# Medidor_Sensor.net
KiCad netlist of a schematic drawn in Altium Designer
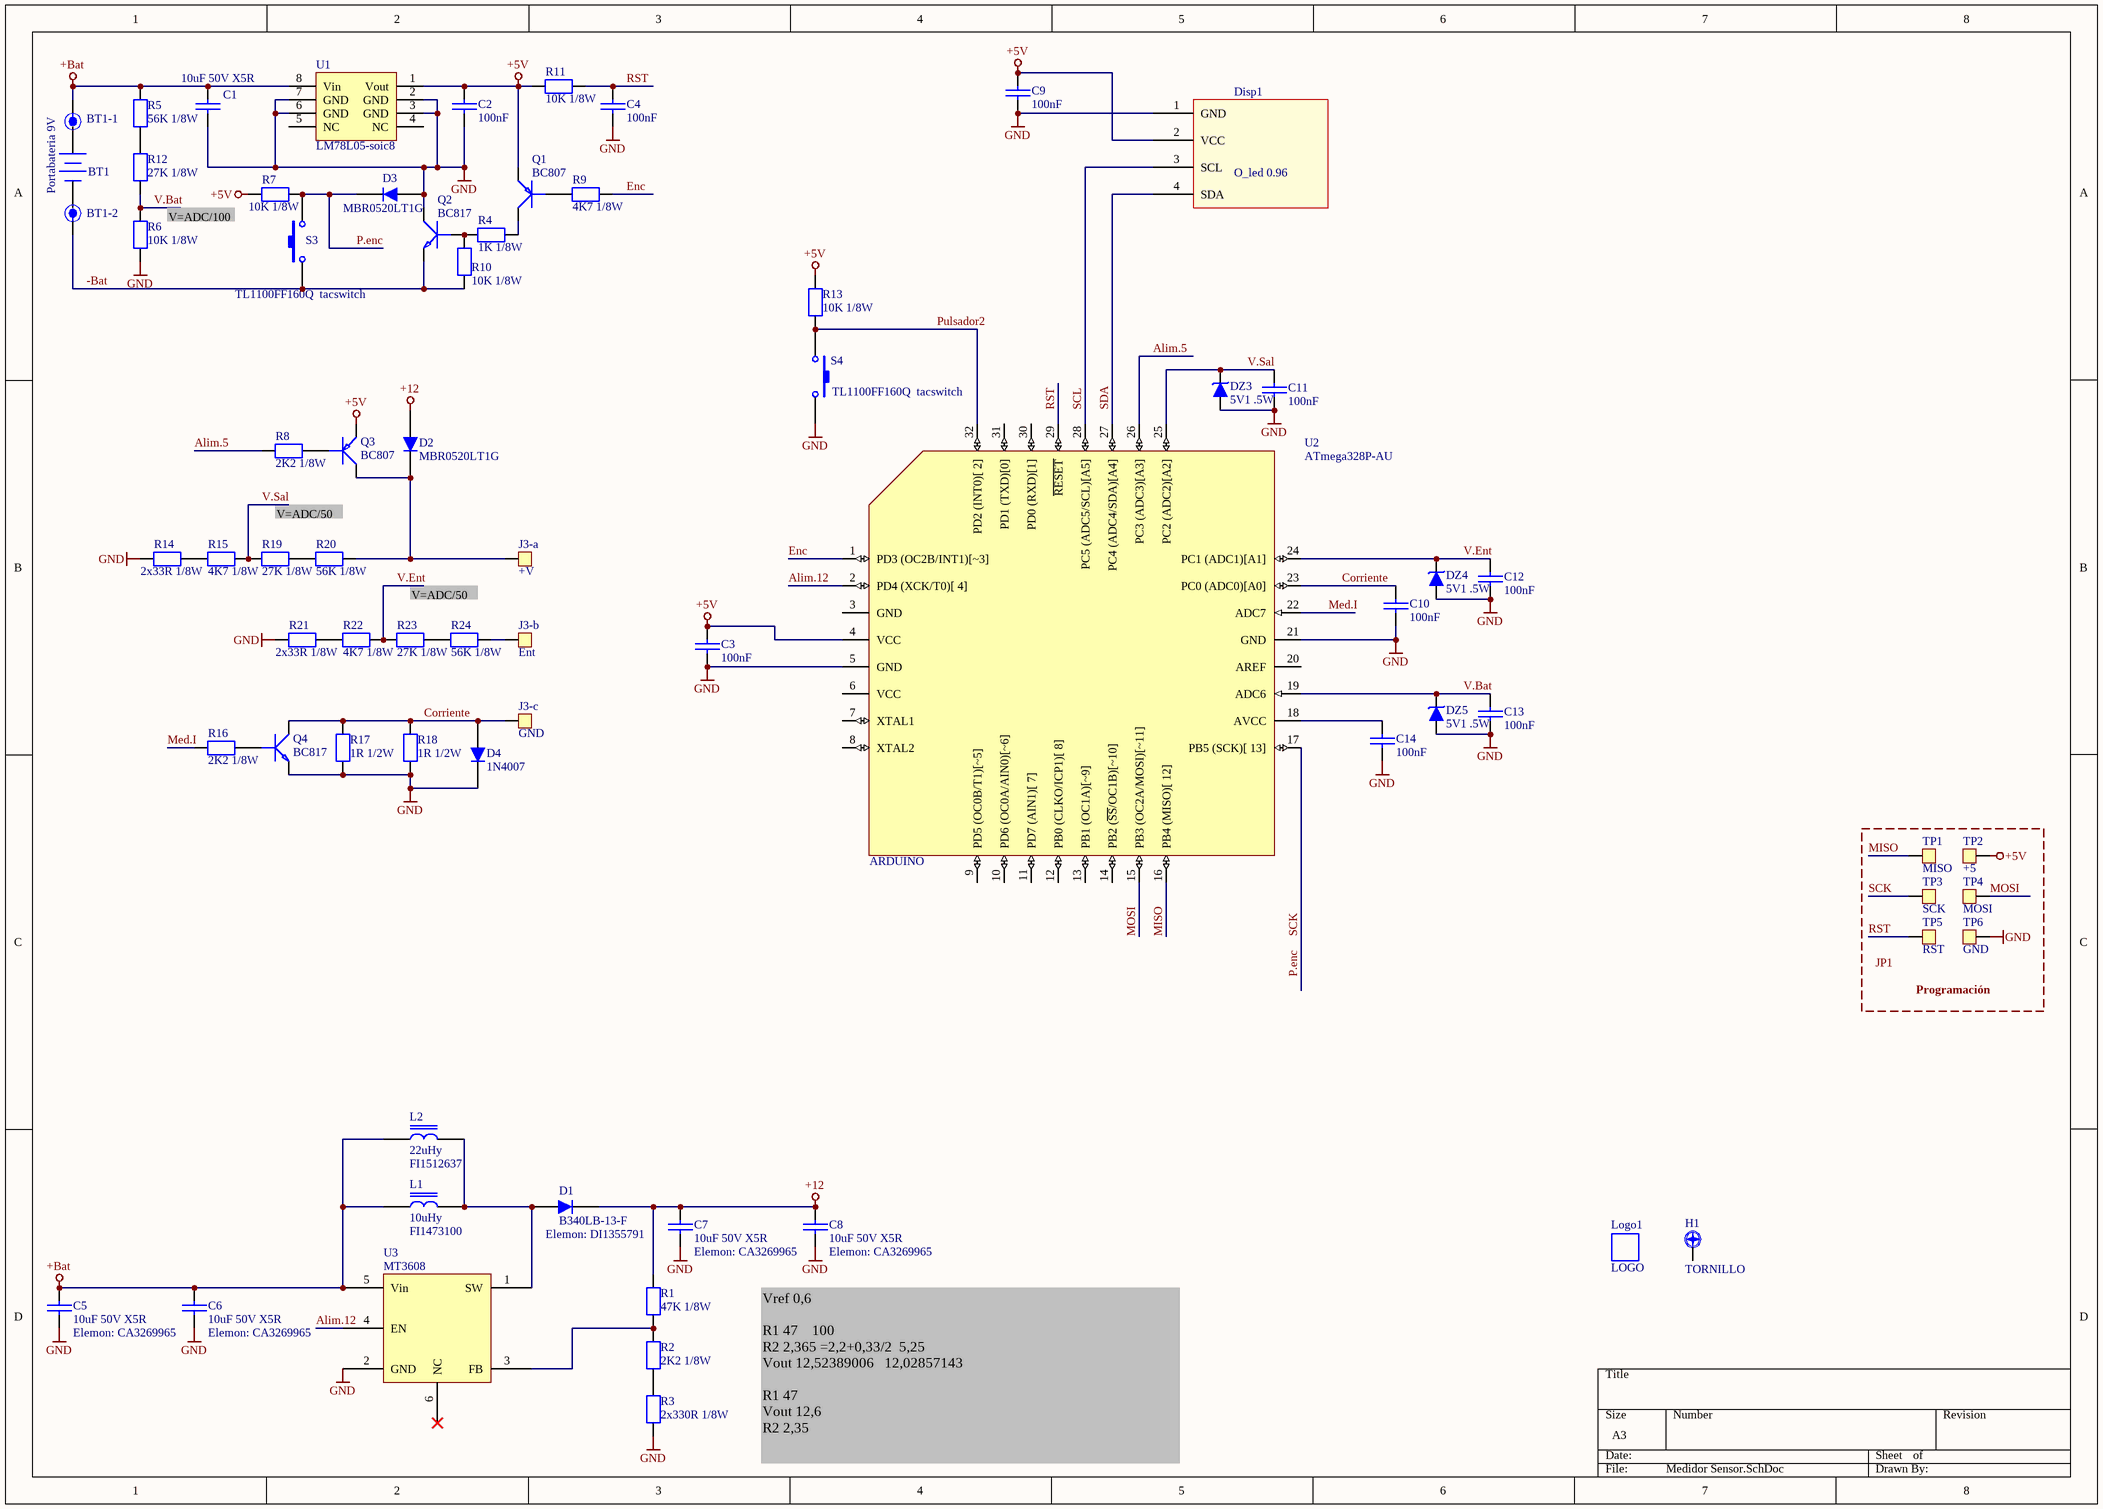
[diagram p0: Medidor Sensor.SchDoc]

(export (version "E")
  (design (tool "Eeschema 10.0.6"))
  (components
    (comp (ref "BT1")
      (value "Portabateria 9V")
      (footprint "BAT-2")
      (description "Multicell Battery")
      (fields (field (name "MANUFACTURER") "Generic Components"))
      (libsource (lib "Miscellaneous Devices") (part "Battery"))
    )
    (comp (ref "BT1-1")
      (value "TEST POINT")
      (footprint "TP_1")
      (description "Tst Point")
      (libsource (lib "") (part "TEST POINT_1"))
    )
    (comp (ref "BT1-2")
      (value "TEST POINT")
      (footprint "TP_1")
      (description "Tst Point")
      (libsource (lib "ACCESORIOSsch") (part "TEST POINT"))
    )
    (comp (ref "C1")
      (value "10uF 50V X5R")
      (footprint "C0805Minimo")
      (description "Capacitor")
      (libsource (lib "CAPACITORESsch") (part "CAP NP"))
    )
    (comp (ref "C2")
      (value "100nF")
      (footprint "C0805Minimo")
      (description "Capacitor")
      (libsource (lib "CAPACITORESsch") (part "CAP NP"))
    )
    (comp (ref "C3")
      (value "100nF")
      (footprint "C0805Minimo")
      (description "Capacitor")
      (libsource (lib "CAPACITORESsch") (part "CAP NP"))
    )
    (comp (ref "C4")
      (value "100nF")
      (footprint "C0805Minimo")
      (description "Capacitor")
      (libsource (lib "CAPACITORESsch") (part "CAP NP"))
    )
    (comp (ref "C5")
      (value "10uF 50V X5R")
      (footprint "C1206")
      (description "Capacitor")
      (fields (field (name "ELEMON") "CA3269965"))
      (libsource (lib "CAPACITORESsch") (part "CAP NP"))
    )
    (comp (ref "C6")
      (value "10uF 50V X5R")
      (footprint "C1206")
      (description "Capacitor")
      (fields (field (name "ELEMON") "CA3269965"))
      (libsource (lib "CAPACITORESsch") (part "CAP NP"))
    )
    (comp (ref "C7")
      (value "10uF 50V X5R")
      (footprint "C1206")
      (description "Capacitor")
      (fields (field (name "ELEMON") "CA3269965"))
      (libsource (lib "CAPACITORESsch") (part "CAP NP"))
    )
    (comp (ref "C8")
      (value "10uF 50V X5R")
      (footprint "C1206")
      (description "Capacitor")
      (fields (field (name "ELEMON") "CA3269965"))
      (libsource (lib "CAPACITORESsch") (part "CAP NP"))
    )
    (comp (ref "C9")
      (value "100nF")
      (footprint "C0805Minimo")
      (description "Capacitor")
      (libsource (lib "CAPACITORESsch") (part "CAP NP"))
    )
    (comp (ref "C10")
      (value "100nF")
      (footprint "C0805Minimo")
      (description "Capacitor")
      (libsource (lib "CAPACITORESsch") (part "CAP NP"))
    )
    (comp (ref "C11")
      (value "100nF")
      (footprint "C0805Minimo")
      (description "Capacitor")
      (libsource (lib "CAPACITORESsch") (part "CAP NP"))
    )
    (comp (ref "C12")
      (value "100nF")
      (footprint "C0805Minimo")
      (description "Capacitor")
      (libsource (lib "CAPACITORESsch") (part "CAP NP"))
    )
    (comp (ref "C13")
      (value "100nF")
      (footprint "C0805Minimo")
      (description "Capacitor")
      (libsource (lib "CAPACITORESsch") (part "CAP NP"))
    )
    (comp (ref "C14")
      (value "100nF")
      (footprint "C0805Minimo")
      (description "Capacitor")
      (libsource (lib "CAPACITORESsch") (part "CAP NP"))
    )
    (comp (ref "D1")
      (value "B340LB-13-F")
      (footprint "smb")
      (description "DIODE")
      (fields (field (name "ELEMON") "DI1355791"))
      (libsource (lib "") (part "DIODE-SMALL_1"))
    )
    (comp (ref "D2")
      (value "MBR0520LT1G")
      (footprint "DL35")
      (description "DIODE")
      (libsource (lib "DIODOSsch") (part "DIODE-SMALL"))
    )
    (comp (ref "D3")
      (value "MBR0520LT1G")
      (footprint "DL35")
      (description "DIODE")
      (libsource (lib "DIODOSsch") (part "DIODE-SMALL"))
    )
    (comp (ref "D4")
      (value "1N4007")
      (footprint "DL45")
      (description "DIODE")
      (libsource (lib "") (part "DIODE-SMALL_1"))
    )
    (comp (ref "Disp1")
      (value "O_led 0.96")
      (footprint "Oled 0.96 Nodotech")
      (description "Disp")
      (libsource (lib "DISPLAYSsch") (part "O_led_0.96"))
    )
    (comp (ref "DZ3")
      (value "5V1 .5W")
      (footprint "DL35")
      (description "Zener Diode")
      (libsource (lib "DIODOSsch") (part "ZENER-SMALL"))
    )
    (comp (ref "DZ4")
      (value "5V1 .5W")
      (footprint "DL35")
      (description "Zener Diode")
      (libsource (lib "DIODOSsch") (part "ZENER-SMALL"))
    )
    (comp (ref "DZ5")
      (value "5V1 .5W")
      (footprint "DL35")
      (description "Zener Diode")
      (libsource (lib "DIODOSsch") (part "ZENER-SMALL"))
    )
    (comp (ref "H1")
      (value "TORNILLO")
      (footprint "Tornillo")
      (description "Tornillo")
      (libsource (lib "ACCESORIOSsch") (part "TORNILLO"))
    )
    (comp (ref "J3-a")
      (value "+V")
      (footprint "TP_1")
      (description "TEST POINT")
      (libsource (lib "CONECTORESsch") (part "TESTPOINT"))
    )
    (comp (ref "J3-b")
      (value "Ent")
      (footprint "TP_1")
      (description "TEST POINT")
      (libsource (lib "CONECTORESsch") (part "TESTPOINT"))
    )
    (comp (ref "J3-c")
      (value "GND")
      (footprint "TP_1")
      (description "TEST POINT")
      (libsource (lib "CONECTORESsch") (part "TESTPOINT"))
    )
    (comp (ref "L1")
      (value "10uHy")
      (footprint "L1210")
      (description "INDUCTOR CHOKE")
      (fields (field (name "ELEMON") "FI1473100"))
      (libsource (lib "INDUCTORESsch") (part "INDUCTOR CHOKE"))
    )
    (comp (ref "L2")
      (value "22uHy")
      (footprint "SMTDR0804")
      (description "INDUCTOR CHOKE")
      (fields (field (name "ELEMON") "FI1512637"))
      (libsource (lib "INDUCTORESsch") (part "INDUCTOR CHOKE"))
    )
    (comp (ref "Logo1")
      (value "LOGO")
      (footprint "IMW Serigrafía")
      (description "Logo Institucional")
      (libsource (lib "ACCESORIOSsch") (part "LOGO"))
    )
    (comp (ref "Q1")
      (value "BC807")
      (footprint "SOT23 - BC817")
      (description "TRANSISTOR")
      (libsource (lib "TRANSISTORESsch") (part "BC807"))
    )
    (comp (ref "Q2")
      (value "BC817")
      (footprint "SOT23 - BC817")
      (description "TRANSISTOR")
      (libsource (lib "TRANSISTORESsch") (part "BC817"))
    )
    (comp (ref "Q3")
      (value "BC807")
      (footprint "SOT23 - BC817")
      (description "TRANSISTOR")
      (libsource (lib "TRANSISTORESsch") (part "BC807"))
    )
    (comp (ref "Q4")
      (value "BC817")
      (footprint "SOT23 - BC817")
      (description "TRANSISTOR")
      (libsource (lib "TRANSISTORESsch") (part "BC817"))
    )
    (comp (ref "R1")
      (value "47K 1/8W")
      (footprint "R0805Minimo")
      (description "Resistencia")
      (libsource (lib "RESISTENCIASsch") (part "RES_SMALL"))
    )
    (comp (ref "R2")
      (value "2K2 1/8W")
      (footprint "R0805Minimo")
      (description "Resistencia")
      (libsource (lib "") (part "RES_SMALL_2"))
    )
    (comp (ref "R3")
      (value "2x330R 1/8W")
      (footprint "R0805Minimo")
      (description "Resistencia")
      (libsource (lib "RESISTENCIASsch") (part "RES_SMALL"))
    )
    (comp (ref "R4")
      (value "1K 1/8W")
      (footprint "R0805Minimo")
      (description "Resistencia")
      (libsource (lib "RESISTENCIASsch") (part "RESISTOR"))
    )
    (comp (ref "R5")
      (value "56K 1/8W")
      (footprint "R0805Minimo")
      (description "Resistencia")
      (libsource (lib "") (part "RESISTOR_2"))
    )
    (comp (ref "R6")
      (value "10K 1/8W")
      (footprint "R0805Minimo")
      (description "Resistencia")
      (libsource (lib "") (part "RESISTOR_2"))
    )
    (comp (ref "R7")
      (value "10K 1/8W")
      (footprint "R0805Minimo")
      (description "Resistencia")
      (libsource (lib "") (part "RESISTOR_3"))
    )
    (comp (ref "R8")
      (value "2K2 1/8W")
      (footprint "R0805Minimo")
      (description "Resistencia")
      (libsource (lib "") (part "RESISTOR_2"))
    )
    (comp (ref "R9")
      (value "4K7 1/8W")
      (footprint "R0805Minimo")
      (description "Resistencia")
      (libsource (lib "") (part "RESISTOR_3"))
    )
    (comp (ref "R10")
      (value "10K 1/8W")
      (footprint "R0805Minimo")
      (description "Resistencia")
      (libsource (lib "") (part "RESISTOR_1"))
    )
    (comp (ref "R11")
      (value "10K 1/8W")
      (footprint "R0805Minimo")
      (description "Resistencia")
      (libsource (lib "") (part "RES_SMALL_1"))
    )
    (comp (ref "R12")
      (value "27K 1/8W")
      (footprint "R0805Minimo")
      (description "Resistencia")
      (libsource (lib "RESISTENCIASsch") (part "RES_SMALL"))
    )
    (comp (ref "R13")
      (value "10K 1/8W")
      (footprint "R0805Minimo")
      (description "Resistencia")
      (libsource (lib "RESISTENCIASsch") (part "RES_SMALL"))
    )
    (comp (ref "R14")
      (value "2x33R 1/8W")
      (footprint "R0805Minimo")
      (description "Resistencia")
      (libsource (lib "RESISTENCIASsch") (part "RESISTOR"))
    )
    (comp (ref "R15")
      (value "4K7 1/8W")
      (footprint "R0805Minimo")
      (description "Resistencia")
      (libsource (lib "RESISTENCIASsch") (part "RESISTOR"))
    )
    (comp (ref "R16")
      (value "2K2 1/8W")
      (footprint "R0805Minimo")
      (description "Resistencia")
      (libsource (lib "") (part "RESISTOR_1"))
    )
    (comp (ref "R17")
      (value "1R 1/2W")
      (footprint "R1210")
      (description "Resistencia")
      (libsource (lib "") (part "RES_SMALL_2"))
    )
    (comp (ref "R18")
      (value "1R 1/2W")
      (footprint "R1210")
      (description "Resistencia")
      (libsource (lib "") (part "RES_SMALL_2"))
    )
    (comp (ref "R19")
      (value "27K 1/8W")
      (footprint "R0805Minimo")
      (description "Resistencia")
      (libsource (lib "") (part "RES_SMALL_1"))
    )
    (comp (ref "R20")
      (value "56K 1/8W")
      (footprint "R0805Minimo")
      (description "Resistencia")
      (libsource (lib "RESISTENCIASsch") (part "RESISTOR"))
    )
    (comp (ref "R21")
      (value "2x33R 1/8W")
      (footprint "R0805Minimo")
      (description "Resistencia")
      (libsource (lib "RESISTENCIASsch") (part "RESISTOR"))
    )
    (comp (ref "R22")
      (value "4K7 1/8W")
      (footprint "R0805Minimo")
      (description "Resistencia")
      (libsource (lib "RESISTENCIASsch") (part "RESISTOR"))
    )
    (comp (ref "R23")
      (value "27K 1/8W")
      (footprint "R0805Minimo")
      (description "Resistencia")
      (libsource (lib "") (part "RES_SMALL_1"))
    )
    (comp (ref "R24")
      (value "56K 1/8W")
      (footprint "R0805Minimo")
      (description "Resistencia")
      (libsource (lib "RESISTENCIASsch") (part "RESISTOR"))
    )
    (comp (ref "S3")
      (value "TL1100FF160Q  tacswitch")
      (footprint "Pul 12x12 Omron B3F")
      (description "Switch")
      (fields (field (name "MANUFACTURER") "Generic Components"))
      (libsource (lib "Miscellaneous Devices") (part "SW-PB"))
    )
    (comp (ref "S4")
      (value "TL1100FF160Q  tacswitch")
      (footprint "Pul 12x12 Omron B3F")
      (description "Switch")
      (fields (field (name "MANUFACTURER") "Generic Components"))
      (libsource (lib "Miscellaneous Devices") (part "SW-PB"))
    )
    (comp (ref "TP1") (value "MISO") (description "TEST POINT") (libsource (lib "") (part "TESTPOINT_2")))
    (comp (ref "TP2") (value "+5") (description "TEST POINT") (libsource (lib "") (part "TESTPOINT_1")))
    (comp (ref "TP3") (value "SCK") (description "TEST POINT") (libsource (lib "") (part "TESTPOINT_2")))
    (comp (ref "TP4") (value "MOSI") (description "TEST POINT") (libsource (lib "") (part "TESTPOINT_1")))
    (comp (ref "TP5") (value "RST") (description "TEST POINT") (libsource (lib "") (part "TESTPOINT_2")))
    (comp (ref "TP6") (value "GND") (description "TEST POINT") (libsource (lib "") (part "TESTPOINT_1")))
    (comp (ref "U1")
      (value "LM78L05-soic8")
      (footprint "SOIC8-150")
      (description "IC")
      (libsource (lib "INTEGRADOSsch") (part "LM78L05-soic8"))
    )
    (comp (ref "U2")
      (value "ATmega328P-AU")
      (footprint "TQFP32")
      (description "IC")
      (fields (field (name "PUBLISHER") "*"))
      (libsource (lib "INTEGRADOSsch") (part "ARDUINO ATmega328P-AU"))
    )
    (comp (ref "U3")
      (value "MT3608")
      (footprint "sot23-6")
      (description "IC")
      (libsource (lib "INTEGRADOSsch") (part "MT3608"))
    )
  )
  (nets
    (net (code "1") (name "+5V") (class "Default")
      (node (ref "C2") (pin "1") (pinfunction "1_1") (pintype "passive"))
      (node (ref "C3") (pin "1") (pinfunction "1_1") (pintype "passive"))
      (node (ref "C9") (pin "1") (pinfunction "1_1") (pintype "passive"))
      (node (ref "Disp1") (pin "2") (pinfunction "VCC_2") (pintype "passive"))
      (node (ref "Q1") (pin "3") (pinfunction "E_3") (pintype "passive"))
      (node (ref "Q3") (pin "3") (pinfunction "E_3") (pintype "passive"))
      (node (ref "R11") (pin "2") (pinfunction "2_2") (pintype "passive"))
      (node (ref "R13") (pin "1") (pinfunction "1_1") (pintype "passive"))
      (node (ref "R7") (pin "2") (pinfunction "2_2") (pintype "passive"))
      (node (ref "TP2") (pin "1") (pinfunction "1_1") (pintype "passive"))
      (node (ref "U1") (pin "1") (pinfunction "Vout_1") (pintype "passive"))
      (node (ref "U2") (pin "4") (pinfunction "VCC_4") (pintype "power_in"))
    )
    (net (code "2") (name "+12") (class "Default")
      (node (ref "C7") (pin "1") (pinfunction "1_1") (pintype "passive"))
      (node (ref "C8") (pin "1") (pinfunction "1_1") (pintype "passive"))
      (node (ref "D1") (pin "2") (pinfunction "2_2") (pintype "passive"))
      (node (ref "D2") (pin "1") (pinfunction "1_1") (pintype "passive"))
      (node (ref "R1") (pin "1") (pinfunction "1_1") (pintype "passive"))
    )
    (net (code "3") (name "+Bat") (class "Default")
      (node (ref "BT1-1") (pin "1") (pinfunction "1_1") (pintype "open_collector"))
      (node (ref "C1") (pin "1") (pinfunction "1_1") (pintype "passive"))
      (node (ref "C5") (pin "1") (pinfunction "1_1") (pintype "passive"))
      (node (ref "C6") (pin "1") (pinfunction "1_1") (pintype "passive"))
      (node (ref "L1") (pin "1") (pinfunction "1_1") (pintype "passive"))
      (node (ref "L2") (pin "1") (pinfunction "1_1") (pintype "passive"))
      (node (ref "R5") (pin "2") (pinfunction "2_2") (pintype "passive"))
      (node (ref "U1") (pin "8") (pinfunction "Vin_8") (pintype "passive"))
      (node (ref "U3") (pin "5") (pinfunction "Vin_5") (pintype "passive"))
    )
    (net (code "4") (name "/-Bat") (class "Default")
      (node (ref "BT1-2") (pin "1") (pinfunction "1_1") (pintype "open_collector"))
      (node (ref "Q2") (pin "3") (pinfunction "E_3") (pintype "passive"))
      (node (ref "R10") (pin "2") (pinfunction "2_2") (pintype "passive"))
      (node (ref "S3") (pin "1") (pinfunction "1_1") (pintype "passive"))
    )
    (net (code "5") (name "/Alim.5") (class "Default")
      (node (ref "R8") (pin "1") (pinfunction "1_1") (pintype "passive"))
      (node (ref "U2") (pin "26") (pinfunction "PC3_(ADC3)[A3]_26") (pintype "bidirectional"))
    )
    (net (code "6") (name "/Alim.12") (class "Default")
      (node (ref "U2") (pin "2") (pinfunction "PD4_(XCK/T0)[_4]_2") (pintype "bidirectional"))
      (node (ref "U3") (pin "4") (pinfunction "EN_4") (pintype "passive"))
    )
    (net (code "7") (name "/Corriente") (class "Default")
      (node (ref "C10") (pin "1") (pinfunction "1_1") (pintype "passive"))
      (node (ref "D4") (pin "1") (pinfunction "1_1") (pintype "passive"))
      (node (ref "J3-c") (pin "1") (pinfunction "1_1") (pintype "passive"))
      (node (ref "Q4") (pin "2") (pinfunction "C_2") (pintype "passive"))
      (node (ref "R17") (pin "2") (pinfunction "2_2") (pintype "passive"))
      (node (ref "R18") (pin "2") (pinfunction "2_2") (pintype "passive"))
      (node (ref "U2") (pin "23") (pinfunction "PC0_(ADC0)[A0]_23") (pintype "bidirectional"))
    )
    (net (code "8") (name "/Enc") (class "Default")
      (node (ref "R9") (pin "1") (pinfunction "1_1") (pintype "passive"))
      (node (ref "U2") (pin "1") (pinfunction "PD3_(OC2B/INT1)[~3]_1") (pintype "bidirectional"))
    )
    (net (code "9") (name "/MISO") (class "Default")
      (node (ref "TP1") (pin "1") (pinfunction "1_1") (pintype "passive"))
      (node (ref "U2") (pin "16") (pinfunction "PB4_(MISO)[_12]_16") (pintype "bidirectional"))
    )
    (net (code "10") (name "/MOSI") (class "Default")
      (node (ref "TP4") (pin "1") (pinfunction "1_1") (pintype "passive"))
      (node (ref "U2") (pin "15") (pinfunction "PB3_(OC2A/MOSI)[~11]_15") (pintype "bidirectional"))
    )
    (net (code "11") (name "/Med.I") (class "Default")
      (node (ref "R16") (pin "2") (pinfunction "2_2") (pintype "passive"))
      (node (ref "U2") (pin "22") (pinfunction "ADC7_22") (pintype "input"))
    )
    (net (code "12") (name "/P.enc") (class "Default")
      (node (ref "D3") (pin "2") (pinfunction "2_2") (pintype "passive"))
      (node (ref "R7") (pin "1") (pinfunction "1_1") (pintype "passive"))
      (node (ref "S3") (pin "2") (pinfunction "2_2") (pintype "passive"))
      (node (ref "TP3") (pin "1") (pinfunction "1_1") (pintype "passive"))
      (node (ref "U2") (pin "17") (pinfunction "PB5_(SCK)[_13]_17") (pintype "bidirectional"))
    )
    (net (code "13") (name "/Pulsador2") (class "Default")
      (node (ref "R13") (pin "2") (pinfunction "2_2") (pintype "passive"))
      (node (ref "S4") (pin "1") (pinfunction "1_1") (pintype "passive"))
      (node (ref "U2") (pin "32") (pinfunction "PD2_(INT0)[_2]_32") (pintype "bidirectional"))
    )
    (net (code "14") (name "/RST") (class "Default")
      (node (ref "C4") (pin "1") (pinfunction "1_1") (pintype "passive"))
      (node (ref "R11") (pin "1") (pinfunction "1_1") (pintype "passive"))
      (node (ref "TP5") (pin "1") (pinfunction "1_1") (pintype "passive"))
      (node (ref "U2") (pin "29") (pinfunction "~{RESET}_29") (pintype "bidirectional"))
    )
    (net (code "15") (name "/SCL") (class "Default")
      (node (ref "Disp1") (pin "3") (pinfunction "SCL_3") (pintype "passive"))
      (node (ref "U2") (pin "28") (pinfunction "PC5_(ADC5/SCL)[A5]_28") (pintype "bidirectional"))
    )
    (net (code "16") (name "/SDA") (class "Default")
      (node (ref "Disp1") (pin "4") (pinfunction "SDA_4") (pintype "passive"))
      (node (ref "U2") (pin "27") (pinfunction "PC4_(ADC4/SDA)[A4]_27") (pintype "bidirectional"))
    )
    (net (code "17") (name "/V.Bat") (class "Default")
      (node (ref "C13") (pin "1") (pinfunction "1_1") (pintype "passive"))
      (node (ref "DZ5") (pin "2") (pinfunction "2_2") (pintype "passive"))
      (node (ref "R12") (pin "2") (pinfunction "2_2") (pintype "passive"))
      (node (ref "R6") (pin "2") (pinfunction "2_2") (pintype "passive"))
      (node (ref "U2") (pin "19") (pinfunction "ADC6_19") (pintype "input"))
    )
    (net (code "18") (name "/V.Ent") (class "Default")
      (node (ref "C12") (pin "1") (pinfunction "1_1") (pintype "passive"))
      (node (ref "DZ4") (pin "2") (pinfunction "2_2") (pintype "passive"))
      (node (ref "R22") (pin "2") (pinfunction "2_2") (pintype "passive"))
      (node (ref "R23") (pin "2") (pinfunction "2_2") (pintype "passive"))
      (node (ref "U2") (pin "24") (pinfunction "PC1_(ADC1)[A1]_24") (pintype "bidirectional"))
    )
    (net (code "19") (name "/V.Sal") (class "Default")
      (node (ref "C11") (pin "1") (pinfunction "1_1") (pintype "passive"))
      (node (ref "DZ3") (pin "2") (pinfunction "2_2") (pintype "passive"))
      (node (ref "R15") (pin "2") (pinfunction "2_2") (pintype "passive"))
      (node (ref "R19") (pin "2") (pinfunction "2_2") (pintype "passive"))
      (node (ref "U2") (pin "25") (pinfunction "PC2_(ADC2)[A2]_25") (pintype "bidirectional"))
    )
    (net (code "20") (name "GND") (class "Default")
      (node (ref "C1") (pin "2") (pinfunction "2_2") (pintype "passive"))
      (node (ref "C10") (pin "2") (pinfunction "2_2") (pintype "passive"))
      (node (ref "C11") (pin "2") (pinfunction "2_2") (pintype "passive"))
      (node (ref "C12") (pin "2") (pinfunction "2_2") (pintype "passive"))
      (node (ref "C13") (pin "2") (pinfunction "2_2") (pintype "passive"))
      (node (ref "C14") (pin "2") (pinfunction "2_2") (pintype "passive"))
      (node (ref "C2") (pin "2") (pinfunction "2_2") (pintype "passive"))
      (node (ref "C3") (pin "2") (pinfunction "2_2") (pintype "passive"))
      (node (ref "C4") (pin "2") (pinfunction "2_2") (pintype "passive"))
      (node (ref "C5") (pin "2") (pinfunction "2_2") (pintype "passive"))
      (node (ref "C6") (pin "2") (pinfunction "2_2") (pintype "passive"))
      (node (ref "C7") (pin "2") (pinfunction "2_2") (pintype "passive"))
      (node (ref "C8") (pin "2") (pinfunction "2_2") (pintype "passive"))
      (node (ref "C9") (pin "2") (pinfunction "2_2") (pintype "passive"))
      (node (ref "D3") (pin "1") (pinfunction "1_1") (pintype "passive"))
      (node (ref "D4") (pin "2") (pinfunction "2_2") (pintype "passive"))
      (node (ref "DZ3") (pin "1") (pinfunction "1_1") (pintype "passive"))
      (node (ref "DZ4") (pin "1") (pinfunction "1_1") (pintype "passive"))
      (node (ref "DZ5") (pin "1") (pinfunction "1_1") (pintype "passive"))
      (node (ref "Disp1") (pin "1") (pinfunction "GND_1") (pintype "passive"))
      (node (ref "Q2") (pin "2") (pinfunction "C_2") (pintype "passive"))
      (node (ref "Q4") (pin "3") (pinfunction "E_3") (pintype "passive"))
      (node (ref "R14") (pin "1") (pinfunction "1_1") (pintype "passive"))
      (node (ref "R17") (pin "1") (pinfunction "1_1") (pintype "passive"))
      (node (ref "R18") (pin "1") (pinfunction "1_1") (pintype "passive"))
      (node (ref "R21") (pin "1") (pinfunction "1_1") (pintype "passive"))
      (node (ref "R3") (pin "2") (pinfunction "2_2") (pintype "passive"))
      (node (ref "R6") (pin "1") (pinfunction "1_1") (pintype "passive"))
      (node (ref "S4") (pin "2") (pinfunction "2_2") (pintype "passive"))
      (node (ref "TP6") (pin "1") (pinfunction "1_1") (pintype "passive"))
      (node (ref "U1") (pin "2") (pinfunction "GND_2") (pintype "passive"))
      (node (ref "U1") (pin "3") (pinfunction "GND_3") (pintype "passive"))
      (node (ref "U1") (pin "6") (pinfunction "GND_6") (pintype "passive"))
      (node (ref "U1") (pin "7") (pinfunction "GND_7") (pintype "passive"))
      (node (ref "U2") (pin "21") (pinfunction "GND_21") (pintype "power_in"))
      (node (ref "U2") (pin "5") (pinfunction "GND_5") (pintype "power_in"))
      (node (ref "U3") (pin "2") (pinfunction "GND_2") (pintype "passive"))
    )
    (net (code "21") (name "Net-(J3-b-Pad1)") (class "Default")
      (node (ref "J3-b") (pin "1") (pinfunction "1_1") (pintype "passive"))
      (node (ref "R24") (pin "2") (pinfunction "2_2") (pintype "passive"))
    )
    (net (code "22") (name "Net-(Q1-B)") (class "Default")
      (node (ref "Q1") (pin "1") (pinfunction "B_1") (pintype "passive"))
      (node (ref "R9") (pin "2") (pinfunction "2_2") (pintype "passive"))
    )
    (net (code "23") (name "Net-(Q1-C)") (class "Default")
      (node (ref "Q1") (pin "2") (pinfunction "C_2") (pintype "passive"))
      (node (ref "R4") (pin "2") (pinfunction "2_2") (pintype "passive"))
    )
    (net (code "24") (name "Net-(Q2-B)") (class "Default")
      (node (ref "Q2") (pin "1") (pinfunction "B_1") (pintype "passive"))
      (node (ref "R10") (pin "1") (pinfunction "1_1") (pintype "passive"))
      (node (ref "R4") (pin "1") (pinfunction "1_1") (pintype "passive"))
    )
    (net (code "25") (name "Net-(Q3-B)") (class "Default")
      (node (ref "Q3") (pin "1") (pinfunction "B_1") (pintype "passive"))
      (node (ref "R8") (pin "2") (pinfunction "2_2") (pintype "passive"))
    )
    (net (code "26") (name "Net-(Q3-C)") (class "Default")
      (node (ref "D2") (pin "2") (pinfunction "2_2") (pintype "passive"))
      (node (ref "J3-a") (pin "1") (pinfunction "1_1") (pintype "passive"))
      (node (ref "Q3") (pin "2") (pinfunction "C_2") (pintype "passive"))
      (node (ref "R20") (pin "2") (pinfunction "2_2") (pintype "passive"))
    )
    (net (code "27") (name "Net-(Q4-B)") (class "Default")
      (node (ref "Q4") (pin "1") (pinfunction "B_1") (pintype "passive"))
      (node (ref "R16") (pin "1") (pinfunction "1_1") (pintype "passive"))
    )
    (net (code "28") (name "Net-(R2-Pad1)") (class "Default")
      (node (ref "R2") (pin "1") (pinfunction "1_1") (pintype "passive"))
      (node (ref "R3") (pin "1") (pinfunction "1_1") (pintype "passive"))
    )
    (net (code "29") (name "Net-(R12-Pad1)") (class "Default")
      (node (ref "R12") (pin "1") (pinfunction "1_1") (pintype "passive"))
      (node (ref "R5") (pin "1") (pinfunction "1_1") (pintype "passive"))
    )
    (net (code "30") (name "Net-(R14-Pad2)") (class "Default")
      (node (ref "R14") (pin "2") (pinfunction "2_2") (pintype "passive"))
      (node (ref "R15") (pin "1") (pinfunction "1_1") (pintype "passive"))
    )
    (net (code "31") (name "Net-(R19-Pad1)") (class "Default")
      (node (ref "R19") (pin "1") (pinfunction "1_1") (pintype "passive"))
      (node (ref "R20") (pin "1") (pinfunction "1_1") (pintype "passive"))
    )
    (net (code "32") (name "Net-(R21-Pad2)") (class "Default")
      (node (ref "R21") (pin "2") (pinfunction "2_2") (pintype "passive"))
      (node (ref "R22") (pin "1") (pinfunction "1_1") (pintype "passive"))
    )
    (net (code "33") (name "Net-(R23-Pad1)") (class "Default")
      (node (ref "R23") (pin "1") (pinfunction "1_1") (pintype "passive"))
      (node (ref "R24") (pin "1") (pinfunction "1_1") (pintype "passive"))
    )
    (net (code "34") (name "Net-(U2-AVCC)") (class "Default")
      (node (ref "C14") (pin "1") (pinfunction "1_1") (pintype "passive"))
      (node (ref "U2") (pin "18") (pinfunction "AVCC_18") (pintype "power_in"))
    )
    (net (code "35") (name "Net-(U3-FB)") (class "Default")
      (node (ref "R1") (pin "2") (pinfunction "2_2") (pintype "passive"))
      (node (ref "R2") (pin "2") (pinfunction "2_2") (pintype "passive"))
      (node (ref "U3") (pin "3") (pinfunction "FB_3") (pintype "passive"))
    )
    (net (code "36") (name "Net-(U3-SW)") (class "Default")
      (node (ref "D1") (pin "1") (pinfunction "1_1") (pintype "passive"))
      (node (ref "L1") (pin "2") (pinfunction "2_2") (pintype "passive"))
      (node (ref "L2") (pin "2") (pinfunction "2_2") (pintype "passive"))
      (node (ref "U3") (pin "1") (pinfunction "SW_1") (pintype "passive"))
    )
    (net (code "37") (name "unconnected-(BT1-+-Pad1)") (class "Default")
      (node (ref "BT1") (pin "1") (pinfunction "+_1") (pintype "passive"))
    )
    (net (code "38") (name "unconnected-(BT1---Pad2)") (class "Default")
      (node (ref "BT1") (pin "2") (pinfunction "-_2") (pintype "passive"))
    )
    (net (code "39") (name "unconnected-(H1-Pad1)") (class "Default")
      (node (ref "H1") (pin "1") (pinfunction "1_1") (pintype "open_collector"))
    )
    (net (code "40") (name "unconnected-(U1-NC-Pad4)") (class "Default")
      (node (ref "U1") (pin "4") (pinfunction "NC_4") (pintype "passive"))
    )
    (net (code "41") (name "unconnected-(U1-NC-Pad5)") (class "Default")
      (node (ref "U1") (pin "5") (pinfunction "NC_5") (pintype "passive"))
    )
    (net (code "42") (name "unconnected-(U2-AREF-Pad20)") (class "Default")
      (node (ref "U2") (pin "20") (pinfunction "AREF_20") (pintype "passive"))
    )
    (net (code "43") (name "unconnected-(U2-GND-Pad3)") (class "Default")
      (node (ref "U2") (pin "3") (pinfunction "GND_3") (pintype "power_in"))
    )
    (net (code "44") (name "unconnected-(U2-PB0_(CLKO{slash}ICP1)[_8]-Pad12)") (class "Default")
      (node (ref "U2") (pin "12") (pinfunction "PB0_(CLKO/ICP1)[_8]_12") (pintype "bidirectional"))
    )
    (net (code "45") (name "unconnected-(U2-PB1_(OC1A)[~9]-Pad13)") (class "Default")
      (node (ref "U2") (pin "13") (pinfunction "PB1_(OC1A)[~9]_13") (pintype "bidirectional"))
    )
    (net (code "46") (name "unconnected-(U2-PB2_(~{SS}{slash}OC1B)[~10]-Pad14)") (class "Default")
      (node (ref "U2") (pin "14") (pinfunction "PB2_(~{SS}/OC1B)[~10]_14") (pintype "bidirectional"))
    )
    (net (code "47") (name "unconnected-(U2-PD0_(RXD)[1]-Pad30)") (class "Default")
      (node (ref "U2") (pin "30") (pinfunction "PD0_(RXD)[1]_30") (pintype "bidirectional"))
    )
    (net (code "48") (name "unconnected-(U2-PD1_(TXD)[0]-Pad31)") (class "Default")
      (node (ref "U2") (pin "31") (pinfunction "PD1_(TXD)[0]_31") (pintype "bidirectional"))
    )
    (net (code "49") (name "unconnected-(U2-PD5_(OC0B{slash}T1)[~5]-Pad9)") (class "Default")
      (node (ref "U2") (pin "9") (pinfunction "PD5_(OC0B/T1)[~5]_9") (pintype "bidirectional"))
    )
    (net (code "50") (name "unconnected-(U2-PD6_(OC0A{slash}AIN0)[~6]-Pad10)") (class "Default")
      (node (ref "U2") (pin "10") (pinfunction "PD6_(OC0A/AIN0)[~6]_10") (pintype "bidirectional"))
    )
    (net (code "51") (name "unconnected-(U2-PD7_(AIN1)[_7]-Pad11)") (class "Default")
      (node (ref "U2") (pin "11") (pinfunction "PD7_(AIN1)[_7]_11") (pintype "bidirectional"))
    )
    (net (code "52") (name "unconnected-(U2-VCC-Pad6)") (class "Default")
      (node (ref "U2") (pin "6") (pinfunction "VCC_6") (pintype "power_in"))
    )
    (net (code "53") (name "unconnected-(U2-XTAL1-Pad7)") (class "Default")
      (node (ref "U2") (pin "7") (pinfunction "XTAL1_7") (pintype "bidirectional"))
    )
    (net (code "54") (name "unconnected-(U2-XTAL2-Pad8)") (class "Default")
      (node (ref "U2") (pin "8") (pinfunction "XTAL2_8") (pintype "bidirectional"))
    )
    (net (code "55") (name "unconnected-(U3-NC-Pad6)") (class "Default")
      (node (ref "U3") (pin "6") (pinfunction "NC_6") (pintype "passive+no_connect"))
    )
  )
)
